# Power_Supply_Schematic_v5.net
KiCad netlist of a schematic drawn in EAGLE
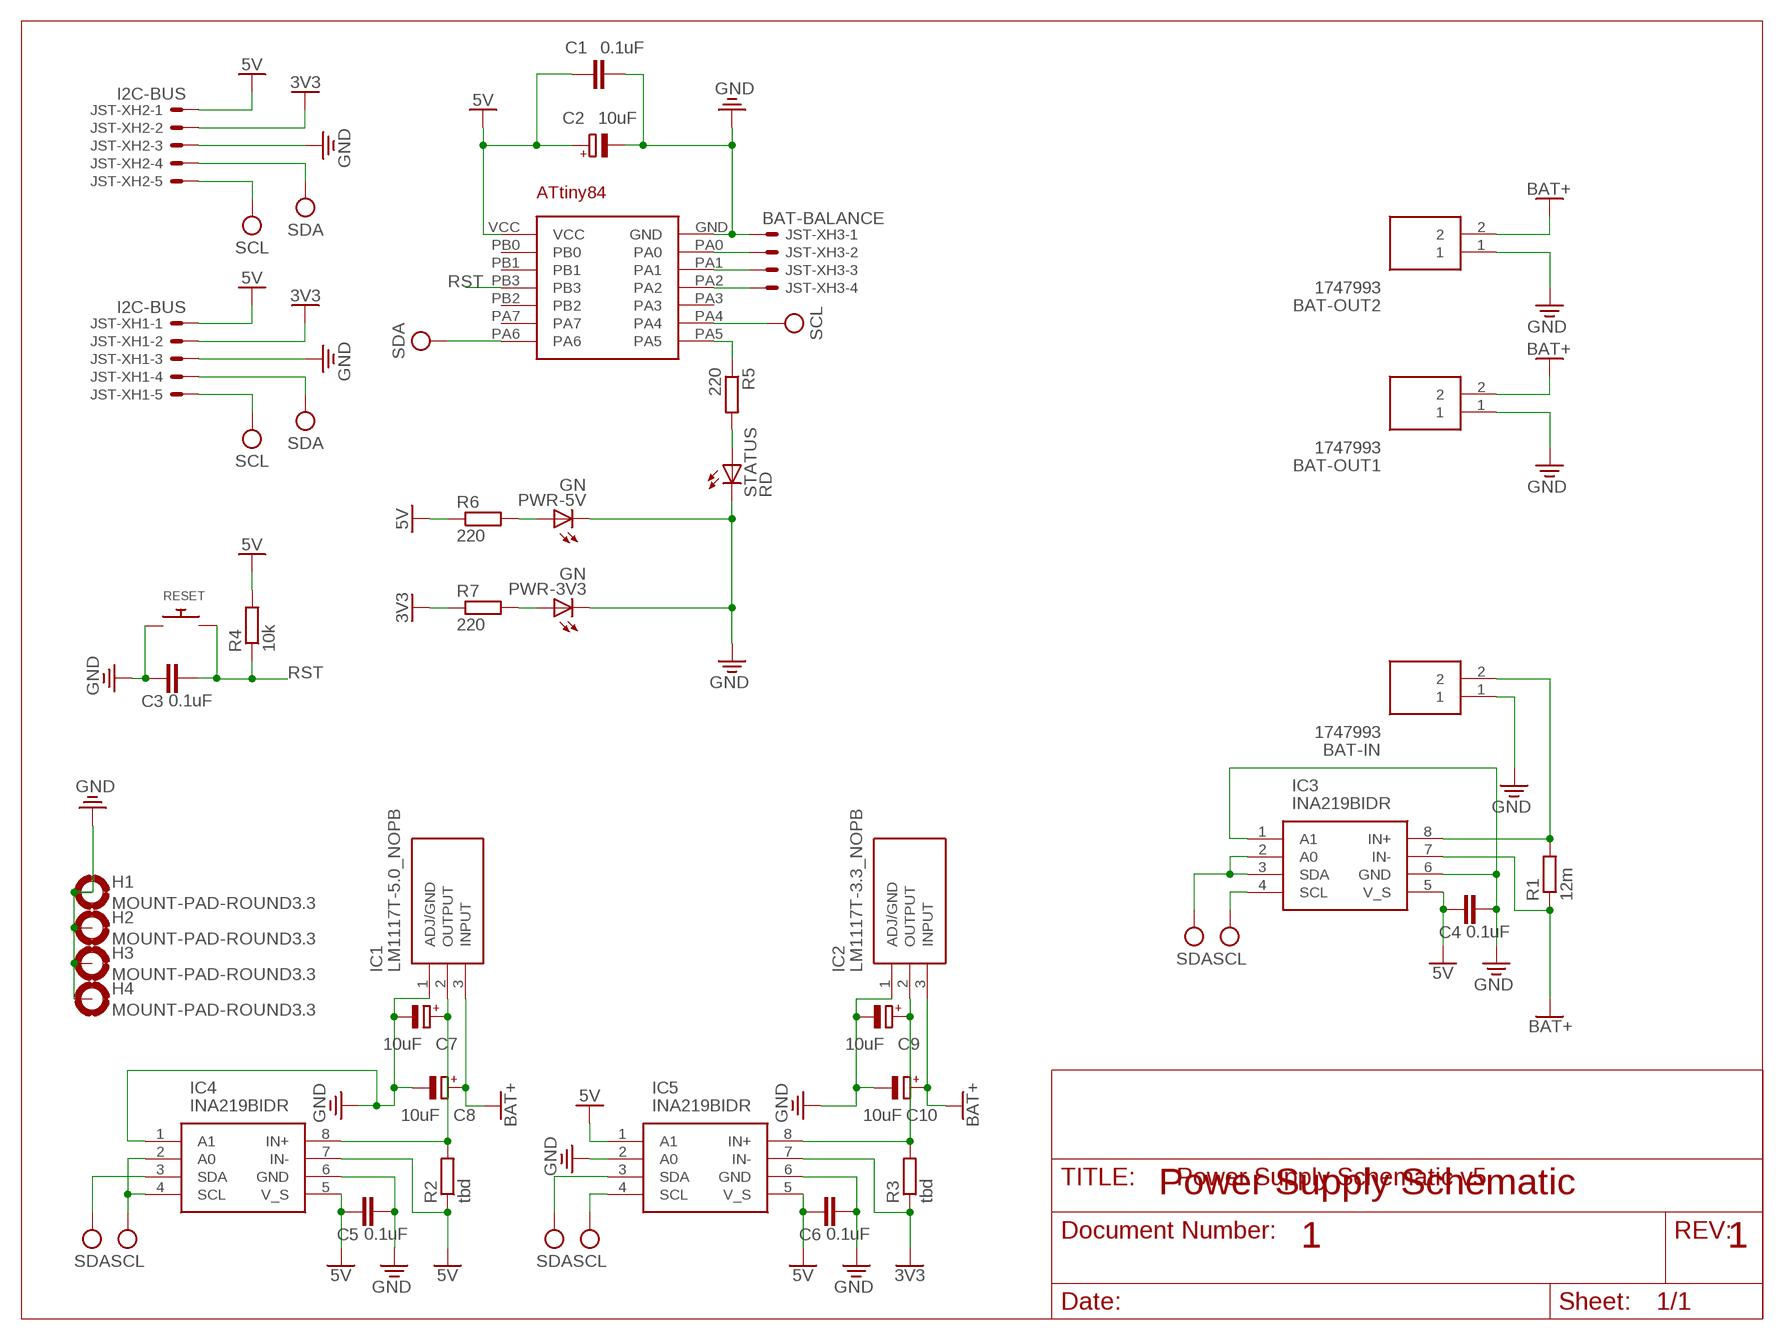
[diagram p0: schematic, sheet 1]

(export (version "E")
  (design (tool "Eeschema 10.0.6"))
  (components
    (comp (ref "BAT-IN")
      (value "1747993")
      (footprint "eagle-import:1747993")
      (fields (field (name "MOUSER_PART_NUMBER") "651-1747993"))
      (libsource (lib "eagle-import") (part "1747993"))
    )
    (comp (ref "BAT-OUT1")
      (value "1747993")
      (footprint "eagle-import:1747993")
      (fields (field (name "MOUSER_PART_NUMBER") "651-1747993"))
      (libsource (lib "eagle-import") (part "1747993"))
    )
    (comp (ref "BAT-OUT2")
      (value "1747993")
      (footprint "eagle-import:1747993")
      (fields (field (name "MOUSER_PART_NUMBER") "651-1747993"))
      (libsource (lib "eagle-import") (part "1747993"))
    )
    (comp (ref "C1")
      (value "0.1uF")
      (footprint "eagle-import:C025-025X050")
      (libsource (lib "eagle-import") (part "C-EU025-025X050"))
    )
    (comp (ref "C2")
      (value "10uF")
      (footprint "eagle-import:E5-10,5")
      (libsource (lib "eagle-import") (part "CPOL-EUE5-10.5"))
    )
    (comp (ref "C3")
      (value "0.1uF")
      (footprint "eagle-import:C025-030X050")
      (libsource (lib "eagle-import") (part "C-EU025-030X050"))
    )
    (comp (ref "C4")
      (value "0.1uF")
      (footprint "eagle-import:C025-030X050")
      (libsource (lib "eagle-import") (part "C-EU025-030X050"))
    )
    (comp (ref "C5")
      (value "0.1uF")
      (footprint "eagle-import:C025-030X050")
      (libsource (lib "eagle-import") (part "C-EU025-030X050"))
    )
    (comp (ref "C6")
      (value "0.1uF")
      (footprint "eagle-import:C025-030X050")
      (libsource (lib "eagle-import") (part "C-EU025-030X050"))
    )
    (comp (ref "C7")
      (value "10uF")
      (footprint "eagle-import:E5-10,5")
      (libsource (lib "eagle-import") (part "CPOL-EUE5-10.5"))
    )
    (comp (ref "C8")
      (value "10uF")
      (footprint "eagle-import:E5-10,5")
      (libsource (lib "eagle-import") (part "CPOL-EUE5-10.5"))
    )
    (comp (ref "C9")
      (value "10uF")
      (footprint "eagle-import:E5-10,5")
      (libsource (lib "eagle-import") (part "CPOL-EUE5-10.5"))
    )
    (comp (ref "C10")
      (value "10uF")
      (footprint "eagle-import:E5-10,5")
      (libsource (lib "eagle-import") (part "CPOL-EUE5-10.5"))
    )
    (comp (ref "H1")
      (value "MOUNT-PAD-ROUND3.3")
      (footprint "eagle-import:3,3-PAD")
      (libsource (lib "eagle-import") (part "MOUNT-PAD-ROUND3.3"))
    )
    (comp (ref "H2")
      (value "MOUNT-PAD-ROUND3.3")
      (footprint "eagle-import:3,3-PAD")
      (libsource (lib "eagle-import") (part "MOUNT-PAD-ROUND3.3"))
    )
    (comp (ref "H3")
      (value "MOUNT-PAD-ROUND3.3")
      (footprint "eagle-import:3,3-PAD")
      (libsource (lib "eagle-import") (part "MOUNT-PAD-ROUND3.3"))
    )
    (comp (ref "H4")
      (value "MOUNT-PAD-ROUND3.3")
      (footprint "eagle-import:3,3-PAD")
      (libsource (lib "eagle-import") (part "MOUNT-PAD-ROUND3.3"))
    )
    (comp (ref "IC1")
      (value "LM1117T-5.0_NOPB")
      (footprint "eagle-import:TO254P470X1028X1955-3P")
      (fields
        (field (name "MANUFACTURER_PART_NUMBER") "LM1117T-5.0/NOPB")
        (field (name "MOUSER2_PART_NUMBER") "926-LM1117T-50/NOPB")
      )
      (libsource (lib "eagle-import") (part "LM1117T-5.0_NOPB"))
    )
    (comp (ref "IC2")
      (value "LM1117T-3.3_NOPB")
      (footprint "eagle-import:TO254P470X1028X1955-3P")
      (fields (field (name "MANUFACTURER_PART_NUMBER") "LM1117T-3.3/NOPB"))
      (libsource (lib "eagle-import") (part "LM1117T-3.3_NOPB"))
    )
    (comp (ref "IC3")
      (value "INA219BIDR")
      (footprint "eagle-import:SOIC127P600X175-8N")
      (fields (field (name "MOUSER_PART_NUMBER") "595-INA219BIDR"))
      (libsource (lib "eagle-import") (part "INA219BIDR"))
    )
    (comp (ref "IC4")
      (value "INA219BIDR")
      (footprint "eagle-import:SOIC127P600X175-8N")
      (fields (field (name "MOUSER_PART_NUMBER") "595-INA219BIDR"))
      (libsource (lib "eagle-import") (part "INA219BIDR"))
    )
    (comp (ref "IC5")
      (value "INA219BIDR")
      (footprint "eagle-import:SOIC127P600X175-8N")
      (fields (field (name "MOUSER_PART_NUMBER") "595-INA219BIDR"))
      (libsource (lib "eagle-import") (part "INA219BIDR"))
    )
    (comp (ref "JST-XH1")
      (value "I2C-BUS")
      (footprint "eagle-import:JST-XH-05-PACKAGE-LONG-PAD")
      (libsource (lib "eagle-import") (part "JST-XH-05-PIN-LONG-PAD"))
    )
    (comp (ref "JST-XH2")
      (value "I2C-BUS")
      (footprint "eagle-import:JST-XH-05-PACKAGE-LONG-PAD")
      (libsource (lib "eagle-import") (part "JST-XH-05-PIN-LONG-PAD"))
    )
    (comp (ref "JST-XH3")
      (value "BAT-BALANCE")
      (footprint "eagle-import:JST-XH-04-PACKAGE-LONG-PAD")
      (libsource (lib "eagle-import") (part "JST-XH-04-PIN-LONG-PAD"))
    )
    (comp (ref "PWR-3V3")
      (value "GN")
      (footprint "eagle-import:LED5MM")
      (libsource (lib "eagle-import") (part "LED5MM"))
    )
    (comp (ref "PWR-5V")
      (value "GN")
      (footprint "eagle-import:LED5MM")
      (libsource (lib "eagle-import") (part "LED5MM"))
    )
    (comp (ref "R1")
      (value "12m")
      (footprint "eagle-import:0204_7")
      (libsource (lib "eagle-import") (part "R-EU_0204/7"))
    )
    (comp (ref "R2")
      (value "tbd")
      (footprint "eagle-import:0204_7")
      (libsource (lib "eagle-import") (part "R-EU_0204/7"))
    )
    (comp (ref "R3")
      (value "tbd")
      (footprint "eagle-import:0204_7")
      (libsource (lib "eagle-import") (part "R-EU_0204/7"))
    )
    (comp (ref "R4")
      (value "10k")
      (footprint "eagle-import:0204_7")
      (libsource (lib "eagle-import") (part "R-EU_0204/7"))
    )
    (comp (ref "R5")
      (value "220")
      (footprint "eagle-import:0204_7")
      (libsource (lib "eagle-import") (part "R-EU_0204/7"))
    )
    (comp (ref "R6")
      (value "220")
      (footprint "eagle-import:0204_7")
      (libsource (lib "eagle-import") (part "R-EU_0204/7"))
    )
    (comp (ref "R7")
      (value "220")
      (footprint "eagle-import:0204_7")
      (libsource (lib "eagle-import") (part "R-EU_0204/7"))
    )
    (comp (ref "RESET")
      (value "SWITCH_PUSHBUTTONEVQ-PE")
      (footprint "eagle-import:TACT_PANA-EVQ")
      (libsource (lib "eagle-import") (part "SWITCH_PUSHBUTTONEVQ-PE"))
    )
    (comp (ref "STATUS")
      (value "RD")
      (footprint "eagle-import:LED5MM")
      (libsource (lib "eagle-import") (part "LED5MM"))
    )
    (comp (ref "U$1")
      (value "ATTINY84DIP")
      (footprint "eagle-import:ATTINY84(DIP)")
      (libsource (lib "eagle-import") (part "ATTINY84DIP"))
    )
  )
  (nets
    (net (code "1") (name "/RST") (class "Default")
      (node (ref "C3") (pin "2") (pinfunction "2_2") (pintype "passive"))
      (node (ref "R4") (pin "1") (pinfunction "1_1") (pintype "passive"))
      (node (ref "RESET") (pin "P$2") (pinfunction "P$2_P$2") (pintype "passive"))
      (node (ref "U$1") (pin "PB3") (pinfunction "PB3_PB3") (pintype "bidirectional"))
    )
    (net (code "2") (name "3V3") (class "Default")
      (node (ref "IC5") (pin "7") (pinfunction "IN-_7") (pintype "bidirectional"))
      (node (ref "JST-XH1") (pin "2") (pinfunction "S_2") (pintype "passive"))
      (node (ref "JST-XH2") (pin "2") (pinfunction "S_2") (pintype "passive"))
      (node (ref "R3") (pin "1") (pinfunction "1_1") (pintype "passive"))
      (node (ref "R7") (pin "1") (pinfunction "1_1") (pintype "passive"))
    )
    (net (code "3") (name "5V") (class "Default")
      (node (ref "C1") (pin "1") (pinfunction "1_1") (pintype "passive"))
      (node (ref "C2") (pin "+") (pinfunction "+_+") (pintype "passive"))
      (node (ref "C4") (pin "1") (pinfunction "1_1") (pintype "passive"))
      (node (ref "C5") (pin "1") (pinfunction "1_1") (pintype "passive"))
      (node (ref "C6") (pin "1") (pinfunction "1_1") (pintype "passive"))
      (node (ref "IC3") (pin "5") (pinfunction "V_S_5") (pintype "bidirectional"))
      (node (ref "IC4") (pin "5") (pinfunction "V_S_5") (pintype "bidirectional"))
      (node (ref "IC4") (pin "7") (pinfunction "IN-_7") (pintype "bidirectional"))
      (node (ref "IC5") (pin "1") (pinfunction "A1_1") (pintype "bidirectional"))
      (node (ref "IC5") (pin "5") (pinfunction "V_S_5") (pintype "bidirectional"))
      (node (ref "JST-XH1") (pin "1") (pinfunction "S_1") (pintype "passive"))
      (node (ref "JST-XH2") (pin "1") (pinfunction "S_1") (pintype "passive"))
      (node (ref "R2") (pin "1") (pinfunction "1_1") (pintype "passive"))
      (node (ref "R4") (pin "2") (pinfunction "2_2") (pintype "passive"))
      (node (ref "R6") (pin "1") (pinfunction "1_1") (pintype "passive"))
      (node (ref "U$1") (pin "VCC") (pinfunction "VCC_VCC") (pintype "bidirectional"))
    )
    (net (code "4") (name "BAT+") (class "Default")
      (node (ref "BAT-OUT1") (pin "2") (pinfunction "2_2") (pintype "bidirectional"))
      (node (ref "BAT-OUT2") (pin "2") (pinfunction "2_2") (pintype "bidirectional"))
      (node (ref "C10") (pin "+") (pinfunction "+_+") (pintype "passive"))
      (node (ref "C8") (pin "+") (pinfunction "+_+") (pintype "passive"))
      (node (ref "IC1") (pin "3") (pinfunction "INPUT_3") (pintype "bidirectional"))
      (node (ref "IC2") (pin "3") (pinfunction "INPUT_3") (pintype "bidirectional"))
      (node (ref "IC3") (pin "7") (pinfunction "IN-_7") (pintype "bidirectional"))
      (node (ref "R1") (pin "1") (pinfunction "1_1") (pintype "passive"))
    )
    (net (code "5") (name "GND") (class "Default")
      (node (ref "BAT-IN") (pin "1") (pinfunction "1_1") (pintype "bidirectional"))
      (node (ref "BAT-OUT1") (pin "1") (pinfunction "1_1") (pintype "bidirectional"))
      (node (ref "BAT-OUT2") (pin "1") (pinfunction "1_1") (pintype "bidirectional"))
      (node (ref "C1") (pin "2") (pinfunction "2_2") (pintype "passive"))
      (node (ref "C10") (pin "-") (pinfunction "-_-") (pintype "passive"))
      (node (ref "C2") (pin "-") (pinfunction "-_-") (pintype "passive"))
      (node (ref "C3") (pin "1") (pinfunction "1_1") (pintype "passive"))
      (node (ref "C4") (pin "2") (pinfunction "2_2") (pintype "passive"))
      (node (ref "C5") (pin "2") (pinfunction "2_2") (pintype "passive"))
      (node (ref "C6") (pin "2") (pinfunction "2_2") (pintype "passive"))
      (node (ref "C7") (pin "-") (pinfunction "-_-") (pintype "passive"))
      (node (ref "C8") (pin "-") (pinfunction "-_-") (pintype "passive"))
      (node (ref "C9") (pin "-") (pinfunction "-_-") (pintype "passive"))
      (node (ref "H1") (pin "B3,3") (pinfunction "MOUNT_B3,3") (pintype "passive"))
      (node (ref "H2") (pin "B3,3") (pinfunction "MOUNT_B3,3") (pintype "passive"))
      (node (ref "H3") (pin "B3,3") (pinfunction "MOUNT_B3,3") (pintype "passive"))
      (node (ref "H4") (pin "B3,3") (pinfunction "MOUNT_B3,3") (pintype "passive"))
      (node (ref "IC1") (pin "1") (pinfunction "ADJ/GND_1") (pintype "bidirectional"))
      (node (ref "IC2") (pin "1") (pinfunction "ADJ/GND_1") (pintype "bidirectional"))
      (node (ref "IC3") (pin "1") (pinfunction "A1_1") (pintype "bidirectional"))
      (node (ref "IC3") (pin "6") (pinfunction "GND_6") (pintype "bidirectional"))
      (node (ref "IC4") (pin "1") (pinfunction "A1_1") (pintype "bidirectional"))
      (node (ref "IC4") (pin "6") (pinfunction "GND_6") (pintype "bidirectional"))
      (node (ref "IC5") (pin "2") (pinfunction "A0_2") (pintype "bidirectional"))
      (node (ref "IC5") (pin "6") (pinfunction "GND_6") (pintype "bidirectional"))
      (node (ref "JST-XH1") (pin "3") (pinfunction "S_3") (pintype "passive"))
      (node (ref "JST-XH2") (pin "3") (pinfunction "S_3") (pintype "passive"))
      (node (ref "JST-XH3") (pin "1") (pinfunction "S_1") (pintype "passive"))
      (node (ref "PWR-3V3") (pin "K") (pinfunction "C_K") (pintype "passive"))
      (node (ref "PWR-5V") (pin "K") (pinfunction "C_K") (pintype "passive"))
      (node (ref "RESET") (pin "P$1") (pinfunction "P$1_P$1") (pintype "passive"))
      (node (ref "STATUS") (pin "K") (pinfunction "C_K") (pintype "passive"))
      (node (ref "U$1") (pin "GND") (pinfunction "GND_GND") (pintype "bidirectional"))
    )
    (net (code "6") (name "Net-(IC1-OUTPUT)") (class "Default")
      (node (ref "C7") (pin "+") (pinfunction "+_+") (pintype "passive"))
      (node (ref "IC1") (pin "2") (pinfunction "OUTPUT_2") (pintype "bidirectional"))
      (node (ref "IC4") (pin "8") (pinfunction "IN+_8") (pintype "bidirectional"))
      (node (ref "R2") (pin "2") (pinfunction "2_2") (pintype "passive"))
    )
    (net (code "7") (name "Net-(IC2-OUTPUT)") (class "Default")
      (node (ref "C9") (pin "+") (pinfunction "+_+") (pintype "passive"))
      (node (ref "IC2") (pin "2") (pinfunction "OUTPUT_2") (pintype "bidirectional"))
      (node (ref "IC5") (pin "8") (pinfunction "IN+_8") (pintype "bidirectional"))
      (node (ref "R3") (pin "2") (pinfunction "2_2") (pintype "passive"))
    )
    (net (code "8") (name "Net-(IC3-IN+)") (class "Default")
      (node (ref "BAT-IN") (pin "2") (pinfunction "2_2") (pintype "bidirectional"))
      (node (ref "IC3") (pin "8") (pinfunction "IN+_8") (pintype "bidirectional"))
      (node (ref "R1") (pin "2") (pinfunction "2_2") (pintype "passive"))
    )
    (net (code "9") (name "Net-(JST-XH3B-S)") (class "Default")
      (node (ref "JST-XH3") (pin "2") (pinfunction "S_2") (pintype "passive"))
      (node (ref "U$1") (pin "PA0") (pinfunction "PA0_PA0") (pintype "bidirectional"))
    )
    (net (code "10") (name "Net-(JST-XH3C-S)") (class "Default")
      (node (ref "JST-XH3") (pin "3") (pinfunction "S_3") (pintype "passive"))
      (node (ref "U$1") (pin "PA1") (pinfunction "PA1_PA1") (pintype "bidirectional"))
    )
    (net (code "11") (name "Net-(JST-XH3D-S)") (class "Default")
      (node (ref "JST-XH3") (pin "4") (pinfunction "S_4") (pintype "passive"))
      (node (ref "U$1") (pin "PA2") (pinfunction "PA2_PA2") (pintype "bidirectional"))
    )
    (net (code "12") (name "Net-(PWR-3V3-PadA)") (class "Default")
      (node (ref "PWR-3V3") (pin "A") (pinfunction "A_A") (pintype "passive"))
      (node (ref "R7") (pin "2") (pinfunction "2_2") (pintype "passive"))
    )
    (net (code "13") (name "Net-(PWR-5V-PadA)") (class "Default")
      (node (ref "PWR-5V") (pin "A") (pinfunction "A_A") (pintype "passive"))
      (node (ref "R6") (pin "2") (pinfunction "2_2") (pintype "passive"))
    )
    (net (code "14") (name "Net-(R5-Pad1)") (class "Default")
      (node (ref "R5") (pin "1") (pinfunction "1_1") (pintype "passive"))
      (node (ref "U$1") (pin "PA5") (pinfunction "PA5_PA5") (pintype "bidirectional"))
    )
    (net (code "15") (name "Net-(R5-Pad2)") (class "Default")
      (node (ref "R5") (pin "2") (pinfunction "2_2") (pintype "passive"))
      (node (ref "STATUS") (pin "A") (pinfunction "A_A") (pintype "passive"))
    )
    (net (code "16") (name "SCL") (class "Default")
      (node (ref "IC3") (pin "4") (pinfunction "SCL_4") (pintype "bidirectional"))
      (node (ref "IC4") (pin "2") (pinfunction "A0_2") (pintype "bidirectional"))
      (node (ref "IC4") (pin "4") (pinfunction "SCL_4") (pintype "bidirectional"))
      (node (ref "IC5") (pin "4") (pinfunction "SCL_4") (pintype "bidirectional"))
      (node (ref "JST-XH1") (pin "5") (pinfunction "S_5") (pintype "passive"))
      (node (ref "JST-XH2") (pin "5") (pinfunction "S_5") (pintype "passive"))
      (node (ref "U$1") (pin "PA4") (pinfunction "PA4_PA4") (pintype "bidirectional"))
    )
    (net (code "17") (name "SDA") (class "Default")
      (node (ref "IC3") (pin "2") (pinfunction "A0_2") (pintype "bidirectional"))
      (node (ref "IC3") (pin "3") (pinfunction "SDA_3") (pintype "bidirectional"))
      (node (ref "IC4") (pin "3") (pinfunction "SDA_3") (pintype "bidirectional"))
      (node (ref "IC5") (pin "3") (pinfunction "SDA_3") (pintype "bidirectional"))
      (node (ref "JST-XH1") (pin "4") (pinfunction "S_4") (pintype "passive"))
      (node (ref "JST-XH2") (pin "4") (pinfunction "S_4") (pintype "passive"))
      (node (ref "U$1") (pin "PA6") (pinfunction "PA6_PA6") (pintype "bidirectional"))
    )
    (net (code "18") (name "unconnected-(U$1-PadPA3)") (class "Default")
      (node (ref "U$1") (pin "PA3") (pinfunction "PA3_PA3") (pintype "bidirectional"))
    )
    (net (code "19") (name "unconnected-(U$1-PadPA7)") (class "Default")
      (node (ref "U$1") (pin "PA7") (pinfunction "PA7_PA7") (pintype "bidirectional"))
    )
    (net (code "20") (name "unconnected-(U$1-PadPB0)") (class "Default")
      (node (ref "U$1") (pin "PB0") (pinfunction "PB0_PB0") (pintype "bidirectional"))
    )
    (net (code "21") (name "unconnected-(U$1-PadPB1)") (class "Default")
      (node (ref "U$1") (pin "PB1") (pinfunction "PB1_PB1") (pintype "bidirectional"))
    )
    (net (code "22") (name "unconnected-(U$1-PadPB2)") (class "Default")
      (node (ref "U$1") (pin "PB2") (pinfunction "PB2_PB2") (pintype "bidirectional"))
    )
  )
)
